# V3.net
KiCad netlist of a schematic drawn in EAGLE
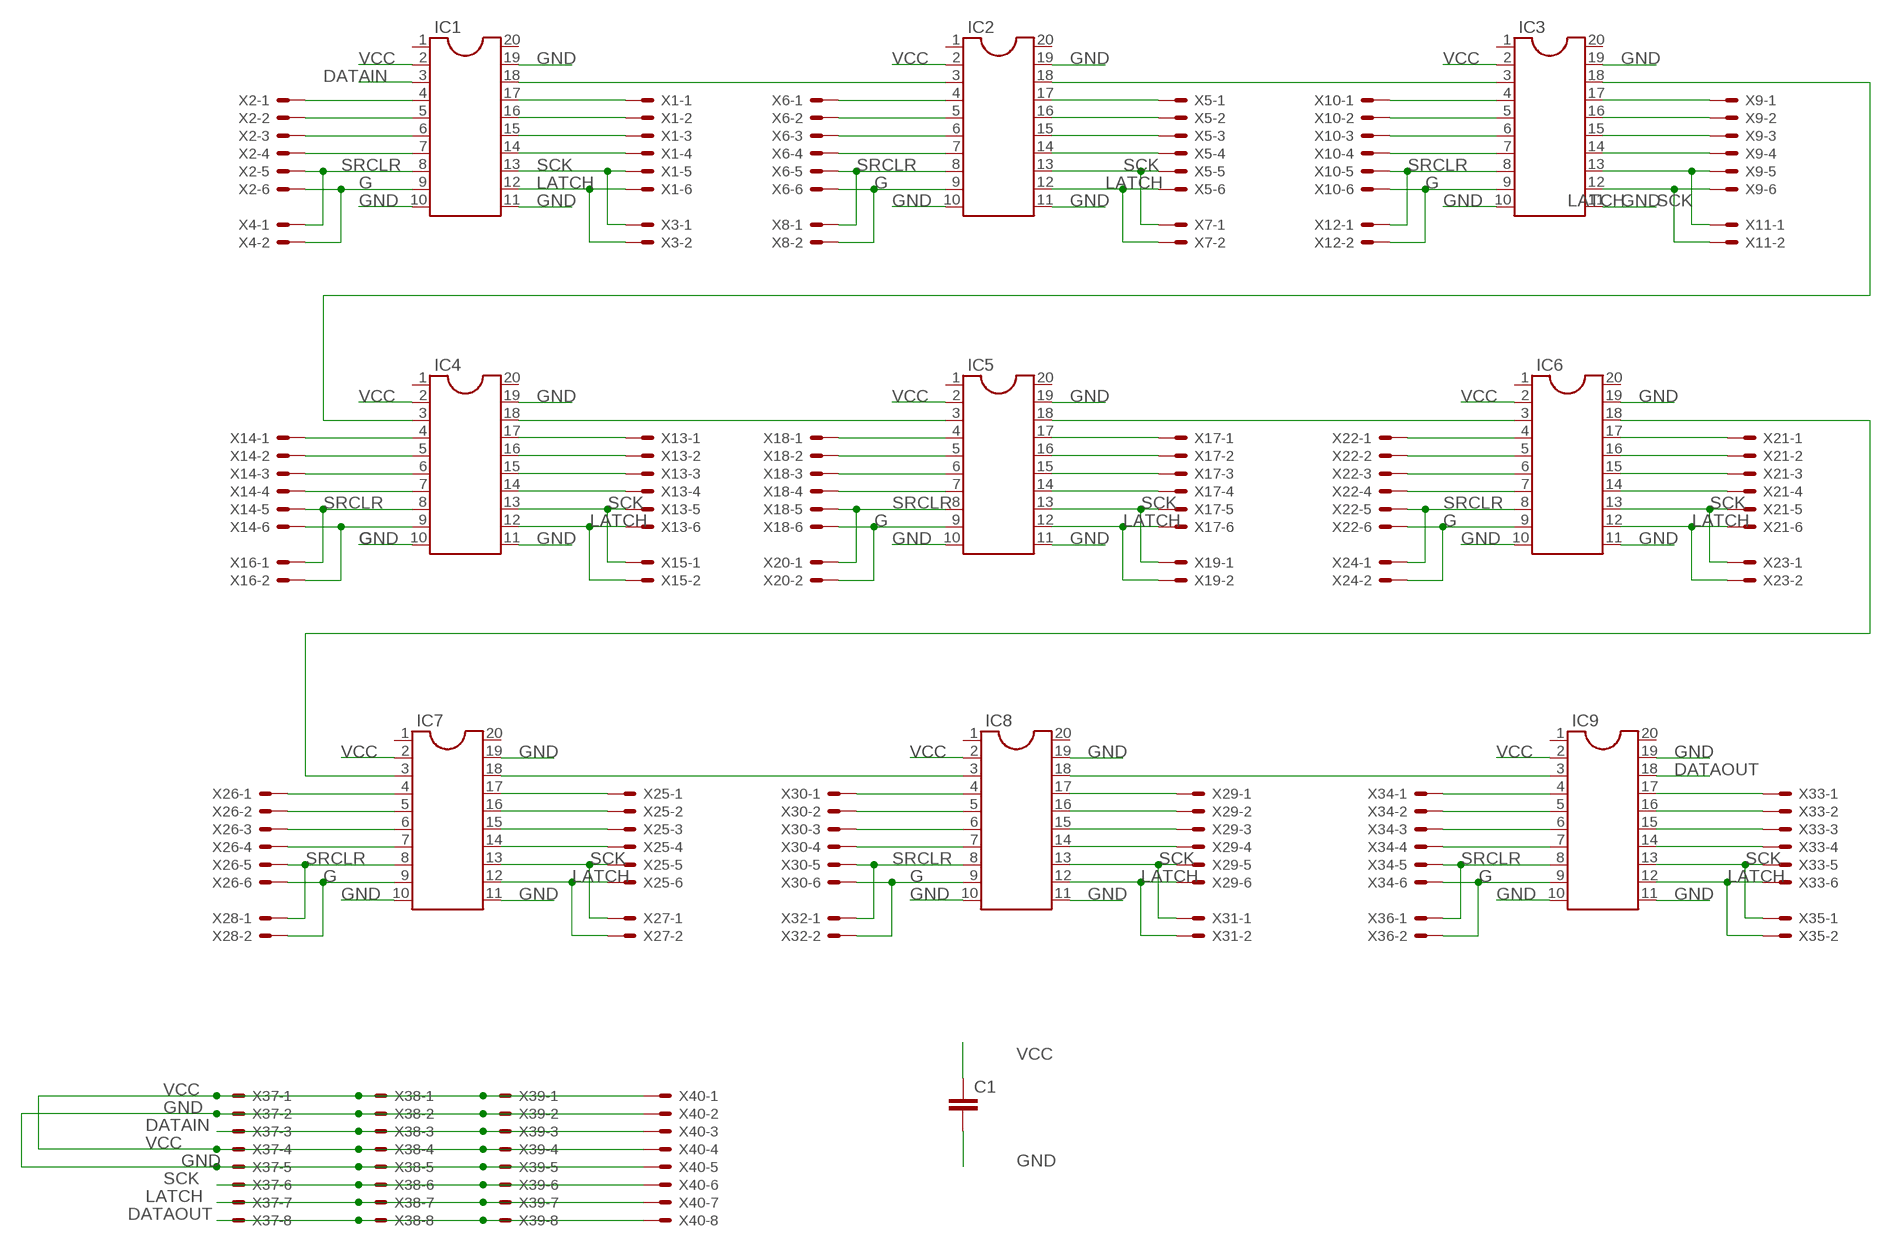
[diagram p0: schematic, sheet 1]

(export (version "E")
  (design (tool "Eeschema 10.0.6"))
  (components
    (comp (ref "C1")
      (value "C2.5/2")
      (footprint "eagle-import:C2.5-2")
      (libsource (lib "eagle-import") (part "C2.5/2"))
    )
    (comp (ref "IC1")
      (value "DIL20")
      (footprint "eagle-import:DIL20")
      (libsource (lib "eagle-import") (part "DIL20"))
    )
    (comp (ref "IC2")
      (value "DIL20")
      (footprint "eagle-import:DIL20")
      (libsource (lib "eagle-import") (part "DIL20"))
    )
    (comp (ref "IC3")
      (value "DIL20")
      (footprint "eagle-import:DIL20")
      (libsource (lib "eagle-import") (part "DIL20"))
    )
    (comp (ref "IC4")
      (value "DIL20")
      (footprint "eagle-import:DIL20")
      (libsource (lib "eagle-import") (part "DIL20"))
    )
    (comp (ref "IC5")
      (value "DIL20")
      (footprint "eagle-import:DIL20")
      (libsource (lib "eagle-import") (part "DIL20"))
    )
    (comp (ref "IC6")
      (value "DIL20")
      (footprint "eagle-import:DIL20")
      (libsource (lib "eagle-import") (part "DIL20"))
    )
    (comp (ref "IC7")
      (value "DIL20")
      (footprint "eagle-import:DIL20")
      (libsource (lib "eagle-import") (part "DIL20"))
    )
    (comp (ref "IC8")
      (value "DIL20")
      (footprint "eagle-import:DIL20")
      (libsource (lib "eagle-import") (part "DIL20"))
    )
    (comp (ref "IC9")
      (value "DIL20")
      (footprint "eagle-import:DIL20")
      (libsource (lib "eagle-import") (part "DIL20"))
    )
    (comp (ref "X1")
      (value "22-23-2061")
      (footprint "eagle-import:22-23-2061")
      (fields (field (name "MF") "MOLEX"))
      (libsource (lib "eagle-import") (part "22-23-2061"))
    )
    (comp (ref "X2")
      (value "22-23-2061")
      (footprint "eagle-import:22-23-2061")
      (fields (field (name "MF") "MOLEX"))
      (libsource (lib "eagle-import") (part "22-23-2061"))
    )
    (comp (ref "X3")
      (value "22-23-2021")
      (footprint "eagle-import:22-23-2021")
      (fields (field (name "MF") "MOLEX"))
      (libsource (lib "eagle-import") (part "22-23-2021"))
    )
    (comp (ref "X4")
      (value "22-23-2021")
      (footprint "eagle-import:22-23-2021")
      (fields (field (name "MF") "MOLEX"))
      (libsource (lib "eagle-import") (part "22-23-2021"))
    )
    (comp (ref "X5")
      (value "22-23-2061")
      (footprint "eagle-import:22-23-2061")
      (fields (field (name "MF") "MOLEX"))
      (libsource (lib "eagle-import") (part "22-23-2061"))
    )
    (comp (ref "X6")
      (value "22-23-2061")
      (footprint "eagle-import:22-23-2061")
      (fields (field (name "MF") "MOLEX"))
      (libsource (lib "eagle-import") (part "22-23-2061"))
    )
    (comp (ref "X7")
      (value "22-23-2021")
      (footprint "eagle-import:22-23-2021")
      (fields (field (name "MF") "MOLEX"))
      (libsource (lib "eagle-import") (part "22-23-2021"))
    )
    (comp (ref "X8")
      (value "22-23-2021")
      (footprint "eagle-import:22-23-2021")
      (fields (field (name "MF") "MOLEX"))
      (libsource (lib "eagle-import") (part "22-23-2021"))
    )
    (comp (ref "X9")
      (value "22-23-2061")
      (footprint "eagle-import:22-23-2061")
      (fields (field (name "MF") "MOLEX"))
      (libsource (lib "eagle-import") (part "22-23-2061"))
    )
    (comp (ref "X10")
      (value "22-23-2061")
      (footprint "eagle-import:22-23-2061")
      (fields (field (name "MF") "MOLEX"))
      (libsource (lib "eagle-import") (part "22-23-2061"))
    )
    (comp (ref "X11")
      (value "22-23-2021")
      (footprint "eagle-import:22-23-2021")
      (fields (field (name "MF") "MOLEX"))
      (libsource (lib "eagle-import") (part "22-23-2021"))
    )
    (comp (ref "X12")
      (value "22-23-2021")
      (footprint "eagle-import:22-23-2021")
      (fields (field (name "MF") "MOLEX"))
      (libsource (lib "eagle-import") (part "22-23-2021"))
    )
    (comp (ref "X13")
      (value "22-23-2061")
      (footprint "eagle-import:22-23-2061")
      (fields (field (name "MF") "MOLEX"))
      (libsource (lib "eagle-import") (part "22-23-2061"))
    )
    (comp (ref "X14")
      (value "22-23-2061")
      (footprint "eagle-import:22-23-2061")
      (fields (field (name "MF") "MOLEX"))
      (libsource (lib "eagle-import") (part "22-23-2061"))
    )
    (comp (ref "X15")
      (value "22-23-2021")
      (footprint "eagle-import:22-23-2021")
      (fields (field (name "MF") "MOLEX"))
      (libsource (lib "eagle-import") (part "22-23-2021"))
    )
    (comp (ref "X16")
      (value "22-23-2021")
      (footprint "eagle-import:22-23-2021")
      (fields (field (name "MF") "MOLEX"))
      (libsource (lib "eagle-import") (part "22-23-2021"))
    )
    (comp (ref "X17")
      (value "22-23-2061")
      (footprint "eagle-import:22-23-2061")
      (fields (field (name "MF") "MOLEX"))
      (libsource (lib "eagle-import") (part "22-23-2061"))
    )
    (comp (ref "X18")
      (value "22-23-2061")
      (footprint "eagle-import:22-23-2061")
      (fields (field (name "MF") "MOLEX"))
      (libsource (lib "eagle-import") (part "22-23-2061"))
    )
    (comp (ref "X19")
      (value "22-23-2021")
      (footprint "eagle-import:22-23-2021")
      (fields (field (name "MF") "MOLEX"))
      (libsource (lib "eagle-import") (part "22-23-2021"))
    )
    (comp (ref "X20")
      (value "22-23-2021")
      (footprint "eagle-import:22-23-2021")
      (fields (field (name "MF") "MOLEX"))
      (libsource (lib "eagle-import") (part "22-23-2021"))
    )
    (comp (ref "X21")
      (value "22-23-2061")
      (footprint "eagle-import:22-23-2061")
      (fields (field (name "MF") "MOLEX"))
      (libsource (lib "eagle-import") (part "22-23-2061"))
    )
    (comp (ref "X22")
      (value "22-23-2061")
      (footprint "eagle-import:22-23-2061")
      (fields (field (name "MF") "MOLEX"))
      (libsource (lib "eagle-import") (part "22-23-2061"))
    )
    (comp (ref "X23")
      (value "22-23-2021")
      (footprint "eagle-import:22-23-2021")
      (fields (field (name "MF") "MOLEX"))
      (libsource (lib "eagle-import") (part "22-23-2021"))
    )
    (comp (ref "X24")
      (value "22-23-2021")
      (footprint "eagle-import:22-23-2021")
      (fields (field (name "MF") "MOLEX"))
      (libsource (lib "eagle-import") (part "22-23-2021"))
    )
    (comp (ref "X25")
      (value "22-23-2061")
      (footprint "eagle-import:22-23-2061")
      (fields (field (name "MF") "MOLEX"))
      (libsource (lib "eagle-import") (part "22-23-2061"))
    )
    (comp (ref "X26")
      (value "22-23-2061")
      (footprint "eagle-import:22-23-2061")
      (fields (field (name "MF") "MOLEX"))
      (libsource (lib "eagle-import") (part "22-23-2061"))
    )
    (comp (ref "X27")
      (value "22-23-2021")
      (footprint "eagle-import:22-23-2021")
      (fields (field (name "MF") "MOLEX"))
      (libsource (lib "eagle-import") (part "22-23-2021"))
    )
    (comp (ref "X28")
      (value "22-23-2021")
      (footprint "eagle-import:22-23-2021")
      (fields (field (name "MF") "MOLEX"))
      (libsource (lib "eagle-import") (part "22-23-2021"))
    )
    (comp (ref "X29")
      (value "22-23-2061")
      (footprint "eagle-import:22-23-2061")
      (fields (field (name "MF") "MOLEX"))
      (libsource (lib "eagle-import") (part "22-23-2061"))
    )
    (comp (ref "X30")
      (value "22-23-2061")
      (footprint "eagle-import:22-23-2061")
      (fields (field (name "MF") "MOLEX"))
      (libsource (lib "eagle-import") (part "22-23-2061"))
    )
    (comp (ref "X31")
      (value "22-23-2021")
      (footprint "eagle-import:22-23-2021")
      (fields (field (name "MF") "MOLEX"))
      (libsource (lib "eagle-import") (part "22-23-2021"))
    )
    (comp (ref "X32")
      (value "22-23-2021")
      (footprint "eagle-import:22-23-2021")
      (fields (field (name "MF") "MOLEX"))
      (libsource (lib "eagle-import") (part "22-23-2021"))
    )
    (comp (ref "X33")
      (value "22-23-2061")
      (footprint "eagle-import:22-23-2061")
      (fields (field (name "MF") "MOLEX"))
      (libsource (lib "eagle-import") (part "22-23-2061"))
    )
    (comp (ref "X34")
      (value "22-23-2061")
      (footprint "eagle-import:22-23-2061")
      (fields (field (name "MF") "MOLEX"))
      (libsource (lib "eagle-import") (part "22-23-2061"))
    )
    (comp (ref "X35")
      (value "22-23-2021")
      (footprint "eagle-import:22-23-2021")
      (fields (field (name "MF") "MOLEX"))
      (libsource (lib "eagle-import") (part "22-23-2021"))
    )
    (comp (ref "X36")
      (value "22-23-2021")
      (footprint "eagle-import:22-23-2021")
      (fields (field (name "MF") "MOLEX"))
      (libsource (lib "eagle-import") (part "22-23-2021"))
    )
    (comp (ref "X37")
      (value "22-23-2081")
      (footprint "eagle-import:22-23-2081")
      (fields (field (name "MF") "MOLEX"))
      (libsource (lib "eagle-import") (part "22-23-2081"))
    )
    (comp (ref "X38")
      (value "22-23-2081")
      (footprint "eagle-import:22-23-2081")
      (fields (field (name "MF") "MOLEX"))
      (libsource (lib "eagle-import") (part "22-23-2081"))
    )
    (comp (ref "X39")
      (value "22-23-2081")
      (footprint "eagle-import:22-23-2081")
      (fields (field (name "MF") "MOLEX"))
      (libsource (lib "eagle-import") (part "22-23-2081"))
    )
    (comp (ref "X40")
      (value "22-23-2081")
      (footprint "eagle-import:22-23-2081")
      (fields (field (name "MF") "MOLEX"))
      (libsource (lib "eagle-import") (part "22-23-2081"))
    )
  )
  (nets
    (net (code "1") (name "/DATAIN") (class "Default")
      (node (ref "IC1") (pin "3") (pinfunction "3_3") (pintype "passive"))
      (node (ref "X37") (pin "3") (pinfunction "S_3") (pintype "passive"))
      (node (ref "X38") (pin "3") (pinfunction "S_3") (pintype "passive"))
      (node (ref "X39") (pin "3") (pinfunction "S_3") (pintype "passive"))
      (node (ref "X40") (pin "3") (pinfunction "S_3") (pintype "passive"))
    )
    (net (code "2") (name "/DATAOUT") (class "Default")
      (node (ref "IC9") (pin "18") (pinfunction "18_18") (pintype "passive"))
      (node (ref "X37") (pin "8") (pinfunction "S_8") (pintype "passive"))
      (node (ref "X38") (pin "8") (pinfunction "S_8") (pintype "passive"))
      (node (ref "X39") (pin "8") (pinfunction "S_8") (pintype "passive"))
      (node (ref "X40") (pin "8") (pinfunction "S_8") (pintype "passive"))
    )
    (net (code "3") (name "/G") (class "Default")
      (node (ref "IC1") (pin "9") (pinfunction "9_9") (pintype "passive"))
      (node (ref "IC2") (pin "9") (pinfunction "9_9") (pintype "passive"))
      (node (ref "IC3") (pin "9") (pinfunction "9_9") (pintype "passive"))
      (node (ref "IC4") (pin "9") (pinfunction "9_9") (pintype "passive"))
      (node (ref "IC5") (pin "9") (pinfunction "9_9") (pintype "passive"))
      (node (ref "IC6") (pin "9") (pinfunction "9_9") (pintype "passive"))
      (node (ref "IC7") (pin "9") (pinfunction "9_9") (pintype "passive"))
      (node (ref "IC8") (pin "9") (pinfunction "9_9") (pintype "passive"))
      (node (ref "IC9") (pin "9") (pinfunction "9_9") (pintype "passive"))
      (node (ref "X10") (pin "6") (pinfunction "S_6") (pintype "passive"))
      (node (ref "X12") (pin "2") (pinfunction "S_2") (pintype "passive"))
      (node (ref "X14") (pin "6") (pinfunction "S_6") (pintype "passive"))
      (node (ref "X16") (pin "2") (pinfunction "S_2") (pintype "passive"))
      (node (ref "X18") (pin "6") (pinfunction "S_6") (pintype "passive"))
      (node (ref "X2") (pin "6") (pinfunction "S_6") (pintype "passive"))
      (node (ref "X20") (pin "2") (pinfunction "S_2") (pintype "passive"))
      (node (ref "X22") (pin "6") (pinfunction "S_6") (pintype "passive"))
      (node (ref "X24") (pin "2") (pinfunction "S_2") (pintype "passive"))
      (node (ref "X26") (pin "6") (pinfunction "S_6") (pintype "passive"))
      (node (ref "X28") (pin "2") (pinfunction "S_2") (pintype "passive"))
      (node (ref "X30") (pin "6") (pinfunction "S_6") (pintype "passive"))
      (node (ref "X32") (pin "2") (pinfunction "S_2") (pintype "passive"))
      (node (ref "X34") (pin "6") (pinfunction "S_6") (pintype "passive"))
      (node (ref "X36") (pin "2") (pinfunction "S_2") (pintype "passive"))
      (node (ref "X4") (pin "2") (pinfunction "S_2") (pintype "passive"))
      (node (ref "X6") (pin "6") (pinfunction "S_6") (pintype "passive"))
      (node (ref "X8") (pin "2") (pinfunction "S_2") (pintype "passive"))
    )
    (net (code "4") (name "/GND") (class "Default")
      (node (ref "C1") (pin "2") (pinfunction "2_2") (pintype "passive"))
      (node (ref "IC1") (pin "10") (pinfunction "10_10") (pintype "passive"))
      (node (ref "IC1") (pin "11") (pinfunction "11_11") (pintype "passive"))
      (node (ref "IC1") (pin "19") (pinfunction "19_19") (pintype "passive"))
      (node (ref "IC2") (pin "10") (pinfunction "10_10") (pintype "passive"))
      (node (ref "IC2") (pin "11") (pinfunction "11_11") (pintype "passive"))
      (node (ref "IC2") (pin "19") (pinfunction "19_19") (pintype "passive"))
      (node (ref "IC3") (pin "10") (pinfunction "10_10") (pintype "passive"))
      (node (ref "IC3") (pin "11") (pinfunction "11_11") (pintype "passive"))
      (node (ref "IC3") (pin "19") (pinfunction "19_19") (pintype "passive"))
      (node (ref "IC4") (pin "10") (pinfunction "10_10") (pintype "passive"))
      (node (ref "IC4") (pin "11") (pinfunction "11_11") (pintype "passive"))
      (node (ref "IC4") (pin "19") (pinfunction "19_19") (pintype "passive"))
      (node (ref "IC5") (pin "10") (pinfunction "10_10") (pintype "passive"))
      (node (ref "IC5") (pin "11") (pinfunction "11_11") (pintype "passive"))
      (node (ref "IC5") (pin "19") (pinfunction "19_19") (pintype "passive"))
      (node (ref "IC6") (pin "10") (pinfunction "10_10") (pintype "passive"))
      (node (ref "IC6") (pin "11") (pinfunction "11_11") (pintype "passive"))
      (node (ref "IC6") (pin "19") (pinfunction "19_19") (pintype "passive"))
      (node (ref "IC7") (pin "10") (pinfunction "10_10") (pintype "passive"))
      (node (ref "IC7") (pin "11") (pinfunction "11_11") (pintype "passive"))
      (node (ref "IC7") (pin "19") (pinfunction "19_19") (pintype "passive"))
      (node (ref "IC8") (pin "10") (pinfunction "10_10") (pintype "passive"))
      (node (ref "IC8") (pin "11") (pinfunction "11_11") (pintype "passive"))
      (node (ref "IC8") (pin "19") (pinfunction "19_19") (pintype "passive"))
      (node (ref "IC9") (pin "10") (pinfunction "10_10") (pintype "passive"))
      (node (ref "IC9") (pin "11") (pinfunction "11_11") (pintype "passive"))
      (node (ref "IC9") (pin "19") (pinfunction "19_19") (pintype "passive"))
      (node (ref "X37") (pin "2") (pinfunction "S_2") (pintype "passive"))
      (node (ref "X37") (pin "5") (pinfunction "S_5") (pintype "passive"))
      (node (ref "X38") (pin "2") (pinfunction "S_2") (pintype "passive"))
      (node (ref "X38") (pin "5") (pinfunction "S_5") (pintype "passive"))
      (node (ref "X39") (pin "2") (pinfunction "S_2") (pintype "passive"))
      (node (ref "X39") (pin "5") (pinfunction "S_5") (pintype "passive"))
      (node (ref "X40") (pin "2") (pinfunction "S_2") (pintype "passive"))
      (node (ref "X40") (pin "5") (pinfunction "S_5") (pintype "passive"))
    )
    (net (code "5") (name "/LATCH") (class "Default")
      (node (ref "IC1") (pin "12") (pinfunction "12_12") (pintype "passive"))
      (node (ref "IC2") (pin "12") (pinfunction "12_12") (pintype "passive"))
      (node (ref "IC3") (pin "12") (pinfunction "12_12") (pintype "passive"))
      (node (ref "IC4") (pin "12") (pinfunction "12_12") (pintype "passive"))
      (node (ref "IC5") (pin "12") (pinfunction "12_12") (pintype "passive"))
      (node (ref "IC6") (pin "12") (pinfunction "12_12") (pintype "passive"))
      (node (ref "IC7") (pin "12") (pinfunction "12_12") (pintype "passive"))
      (node (ref "IC8") (pin "12") (pinfunction "12_12") (pintype "passive"))
      (node (ref "IC9") (pin "12") (pinfunction "12_12") (pintype "passive"))
      (node (ref "X1") (pin "6") (pinfunction "S_6") (pintype "passive"))
      (node (ref "X11") (pin "2") (pinfunction "S_2") (pintype "passive"))
      (node (ref "X13") (pin "6") (pinfunction "S_6") (pintype "passive"))
      (node (ref "X15") (pin "2") (pinfunction "S_2") (pintype "passive"))
      (node (ref "X17") (pin "6") (pinfunction "S_6") (pintype "passive"))
      (node (ref "X19") (pin "2") (pinfunction "S_2") (pintype "passive"))
      (node (ref "X21") (pin "6") (pinfunction "S_6") (pintype "passive"))
      (node (ref "X23") (pin "2") (pinfunction "S_2") (pintype "passive"))
      (node (ref "X25") (pin "6") (pinfunction "S_6") (pintype "passive"))
      (node (ref "X27") (pin "2") (pinfunction "S_2") (pintype "passive"))
      (node (ref "X29") (pin "6") (pinfunction "S_6") (pintype "passive"))
      (node (ref "X3") (pin "2") (pinfunction "S_2") (pintype "passive"))
      (node (ref "X31") (pin "2") (pinfunction "S_2") (pintype "passive"))
      (node (ref "X33") (pin "6") (pinfunction "S_6") (pintype "passive"))
      (node (ref "X35") (pin "2") (pinfunction "S_2") (pintype "passive"))
      (node (ref "X37") (pin "7") (pinfunction "S_7") (pintype "passive"))
      (node (ref "X38") (pin "7") (pinfunction "S_7") (pintype "passive"))
      (node (ref "X39") (pin "7") (pinfunction "S_7") (pintype "passive"))
      (node (ref "X40") (pin "7") (pinfunction "S_7") (pintype "passive"))
      (node (ref "X5") (pin "6") (pinfunction "S_6") (pintype "passive"))
      (node (ref "X7") (pin "2") (pinfunction "S_2") (pintype "passive"))
      (node (ref "X9") (pin "6") (pinfunction "S_6") (pintype "passive"))
    )
    (net (code "6") (name "/SCK") (class "Default")
      (node (ref "IC1") (pin "13") (pinfunction "13_13") (pintype "passive"))
      (node (ref "IC2") (pin "13") (pinfunction "13_13") (pintype "passive"))
      (node (ref "IC3") (pin "13") (pinfunction "13_13") (pintype "passive"))
      (node (ref "IC4") (pin "13") (pinfunction "13_13") (pintype "passive"))
      (node (ref "IC5") (pin "13") (pinfunction "13_13") (pintype "passive"))
      (node (ref "IC6") (pin "13") (pinfunction "13_13") (pintype "passive"))
      (node (ref "IC7") (pin "13") (pinfunction "13_13") (pintype "passive"))
      (node (ref "IC8") (pin "13") (pinfunction "13_13") (pintype "passive"))
      (node (ref "IC9") (pin "13") (pinfunction "13_13") (pintype "passive"))
      (node (ref "X1") (pin "5") (pinfunction "S_5") (pintype "passive"))
      (node (ref "X11") (pin "1") (pinfunction "S_1") (pintype "passive"))
      (node (ref "X13") (pin "5") (pinfunction "S_5") (pintype "passive"))
      (node (ref "X15") (pin "1") (pinfunction "S_1") (pintype "passive"))
      (node (ref "X17") (pin "5") (pinfunction "S_5") (pintype "passive"))
      (node (ref "X19") (pin "1") (pinfunction "S_1") (pintype "passive"))
      (node (ref "X21") (pin "5") (pinfunction "S_5") (pintype "passive"))
      (node (ref "X23") (pin "1") (pinfunction "S_1") (pintype "passive"))
      (node (ref "X25") (pin "5") (pinfunction "S_5") (pintype "passive"))
      (node (ref "X27") (pin "1") (pinfunction "S_1") (pintype "passive"))
      (node (ref "X29") (pin "5") (pinfunction "S_5") (pintype "passive"))
      (node (ref "X3") (pin "1") (pinfunction "S_1") (pintype "passive"))
      (node (ref "X31") (pin "1") (pinfunction "S_1") (pintype "passive"))
      (node (ref "X33") (pin "5") (pinfunction "S_5") (pintype "passive"))
      (node (ref "X35") (pin "1") (pinfunction "S_1") (pintype "passive"))
      (node (ref "X37") (pin "6") (pinfunction "S_6") (pintype "passive"))
      (node (ref "X38") (pin "6") (pinfunction "S_6") (pintype "passive"))
      (node (ref "X39") (pin "6") (pinfunction "S_6") (pintype "passive"))
      (node (ref "X40") (pin "6") (pinfunction "S_6") (pintype "passive"))
      (node (ref "X5") (pin "5") (pinfunction "S_5") (pintype "passive"))
      (node (ref "X7") (pin "1") (pinfunction "S_1") (pintype "passive"))
      (node (ref "X9") (pin "5") (pinfunction "S_5") (pintype "passive"))
    )
    (net (code "7") (name "/SRCLR") (class "Default")
      (node (ref "IC1") (pin "8") (pinfunction "8_8") (pintype "passive"))
      (node (ref "IC2") (pin "8") (pinfunction "8_8") (pintype "passive"))
      (node (ref "IC3") (pin "8") (pinfunction "8_8") (pintype "passive"))
      (node (ref "IC4") (pin "8") (pinfunction "8_8") (pintype "passive"))
      (node (ref "IC5") (pin "8") (pinfunction "8_8") (pintype "passive"))
      (node (ref "IC6") (pin "8") (pinfunction "8_8") (pintype "passive"))
      (node (ref "IC7") (pin "8") (pinfunction "8_8") (pintype "passive"))
      (node (ref "IC8") (pin "8") (pinfunction "8_8") (pintype "passive"))
      (node (ref "IC9") (pin "8") (pinfunction "8_8") (pintype "passive"))
      (node (ref "X10") (pin "5") (pinfunction "S_5") (pintype "passive"))
      (node (ref "X12") (pin "1") (pinfunction "S_1") (pintype "passive"))
      (node (ref "X14") (pin "5") (pinfunction "S_5") (pintype "passive"))
      (node (ref "X16") (pin "1") (pinfunction "S_1") (pintype "passive"))
      (node (ref "X18") (pin "5") (pinfunction "S_5") (pintype "passive"))
      (node (ref "X2") (pin "5") (pinfunction "S_5") (pintype "passive"))
      (node (ref "X20") (pin "1") (pinfunction "S_1") (pintype "passive"))
      (node (ref "X22") (pin "5") (pinfunction "S_5") (pintype "passive"))
      (node (ref "X24") (pin "1") (pinfunction "S_1") (pintype "passive"))
      (node (ref "X26") (pin "5") (pinfunction "S_5") (pintype "passive"))
      (node (ref "X28") (pin "1") (pinfunction "S_1") (pintype "passive"))
      (node (ref "X30") (pin "5") (pinfunction "S_5") (pintype "passive"))
      (node (ref "X32") (pin "1") (pinfunction "S_1") (pintype "passive"))
      (node (ref "X34") (pin "5") (pinfunction "S_5") (pintype "passive"))
      (node (ref "X36") (pin "1") (pinfunction "S_1") (pintype "passive"))
      (node (ref "X4") (pin "1") (pinfunction "S_1") (pintype "passive"))
      (node (ref "X6") (pin "5") (pinfunction "S_5") (pintype "passive"))
      (node (ref "X8") (pin "1") (pinfunction "S_1") (pintype "passive"))
    )
    (net (code "8") (name "/VCC") (class "Default")
      (node (ref "C1") (pin "1") (pinfunction "1_1") (pintype "passive"))
      (node (ref "IC1") (pin "2") (pinfunction "2_2") (pintype "passive"))
      (node (ref "IC2") (pin "2") (pinfunction "2_2") (pintype "passive"))
      (node (ref "IC3") (pin "2") (pinfunction "2_2") (pintype "passive"))
      (node (ref "IC4") (pin "2") (pinfunction "2_2") (pintype "passive"))
      (node (ref "IC5") (pin "2") (pinfunction "2_2") (pintype "passive"))
      (node (ref "IC6") (pin "2") (pinfunction "2_2") (pintype "passive"))
      (node (ref "IC7") (pin "2") (pinfunction "2_2") (pintype "passive"))
      (node (ref "IC8") (pin "2") (pinfunction "2_2") (pintype "passive"))
      (node (ref "IC9") (pin "2") (pinfunction "2_2") (pintype "passive"))
      (node (ref "X37") (pin "1") (pinfunction "S_1") (pintype "passive"))
      (node (ref "X37") (pin "4") (pinfunction "S_4") (pintype "passive"))
      (node (ref "X38") (pin "1") (pinfunction "S_1") (pintype "passive"))
      (node (ref "X38") (pin "4") (pinfunction "S_4") (pintype "passive"))
      (node (ref "X39") (pin "1") (pinfunction "S_1") (pintype "passive"))
      (node (ref "X39") (pin "4") (pinfunction "S_4") (pintype "passive"))
      (node (ref "X40") (pin "1") (pinfunction "S_1") (pintype "passive"))
      (node (ref "X40") (pin "4") (pinfunction "S_4") (pintype "passive"))
    )
    (net (code "9") (name "Net-(IC1-Pad18)") (class "Default")
      (node (ref "IC1") (pin "18") (pinfunction "18_18") (pintype "passive"))
      (node (ref "IC2") (pin "3") (pinfunction "3_3") (pintype "passive"))
    )
    (net (code "10") (name "Net-(IC2-Pad18)") (class "Default")
      (node (ref "IC2") (pin "18") (pinfunction "18_18") (pintype "passive"))
      (node (ref "IC3") (pin "3") (pinfunction "3_3") (pintype "passive"))
    )
    (net (code "11") (name "Net-(IC3-Pad18)") (class "Default")
      (node (ref "IC3") (pin "18") (pinfunction "18_18") (pintype "passive"))
      (node (ref "IC4") (pin "3") (pinfunction "3_3") (pintype "passive"))
    )
    (net (code "12") (name "Net-(IC4-Pad18)") (class "Default")
      (node (ref "IC4") (pin "18") (pinfunction "18_18") (pintype "passive"))
      (node (ref "IC5") (pin "3") (pinfunction "3_3") (pintype "passive"))
    )
    (net (code "13") (name "Net-(IC5-Pad18)") (class "Default")
      (node (ref "IC5") (pin "18") (pinfunction "18_18") (pintype "passive"))
      (node (ref "IC6") (pin "3") (pinfunction "3_3") (pintype "passive"))
    )
    (net (code "14") (name "Net-(IC6-Pad18)") (class "Default")
      (node (ref "IC6") (pin "18") (pinfunction "18_18") (pintype "passive"))
      (node (ref "IC7") (pin "3") (pinfunction "3_3") (pintype "passive"))
    )
    (net (code "15") (name "Net-(IC7-Pad18)") (class "Default")
      (node (ref "IC7") (pin "18") (pinfunction "18_18") (pintype "passive"))
      (node (ref "IC8") (pin "3") (pinfunction "3_3") (pintype "passive"))
    )
    (net (code "16") (name "Net-(IC8-Pad18)") (class "Default")
      (node (ref "IC8") (pin "18") (pinfunction "18_18") (pintype "passive"))
      (node (ref "IC9") (pin "3") (pinfunction "3_3") (pintype "passive"))
    )
    (net (code "17") (name "Net-(X1A-S)") (class "Default")
      (node (ref "IC1") (pin "17") (pinfunction "17_17") (pintype "passive"))
      (node (ref "X1") (pin "1") (pinfunction "S_1") (pintype "passive"))
    )
    (net (code "18") (name "Net-(X1B-S)") (class "Default")
      (node (ref "IC1") (pin "16") (pinfunction "16_16") (pintype "passive"))
      (node (ref "X1") (pin "2") (pinfunction "S_2") (pintype "passive"))
    )
    (net (code "19") (name "Net-(X1C-S)") (class "Default")
      (node (ref "IC1") (pin "15") (pinfunction "15_15") (pintype "passive"))
      (node (ref "X1") (pin "3") (pinfunction "S_3") (pintype "passive"))
    )
    (net (code "20") (name "Net-(X1D-S)") (class "Default")
      (node (ref "IC1") (pin "14") (pinfunction "14_14") (pintype "passive"))
      (node (ref "X1") (pin "4") (pinfunction "S_4") (pintype "passive"))
    )
    (net (code "21") (name "Net-(X2A-S)") (class "Default")
      (node (ref "IC1") (pin "4") (pinfunction "4_4") (pintype "passive"))
      (node (ref "X2") (pin "1") (pinfunction "S_1") (pintype "passive"))
    )
    (net (code "22") (name "Net-(X2B-S)") (class "Default")
      (node (ref "IC1") (pin "5") (pinfunction "5_5") (pintype "passive"))
      (node (ref "X2") (pin "2") (pinfunction "S_2") (pintype "passive"))
    )
    (net (code "23") (name "Net-(X2C-S)") (class "Default")
      (node (ref "IC1") (pin "6") (pinfunction "6_6") (pintype "passive"))
      (node (ref "X2") (pin "3") (pinfunction "S_3") (pintype "passive"))
    )
    (net (code "24") (name "Net-(X2D-S)") (class "Default")
      (node (ref "IC1") (pin "7") (pinfunction "7_7") (pintype "passive"))
      (node (ref "X2") (pin "4") (pinfunction "S_4") (pintype "passive"))
    )
    (net (code "25") (name "Net-(X5A-S)") (class "Default")
      (node (ref "IC2") (pin "17") (pinfunction "17_17") (pintype "passive"))
      (node (ref "X5") (pin "1") (pinfunction "S_1") (pintype "passive"))
    )
    (net (code "26") (name "Net-(X5B-S)") (class "Default")
      (node (ref "IC2") (pin "16") (pinfunction "16_16") (pintype "passive"))
      (node (ref "X5") (pin "2") (pinfunction "S_2") (pintype "passive"))
    )
    (net (code "27") (name "Net-(X5C-S)") (class "Default")
      (node (ref "IC2") (pin "15") (pinfunction "15_15") (pintype "passive"))
      (node (ref "X5") (pin "3") (pinfunction "S_3") (pintype "passive"))
    )
    (net (code "28") (name "Net-(X5D-S)") (class "Default")
      (node (ref "IC2") (pin "14") (pinfunction "14_14") (pintype "passive"))
      (node (ref "X5") (pin "4") (pinfunction "S_4") (pintype "passive"))
    )
    (net (code "29") (name "Net-(X6A-S)") (class "Default")
      (node (ref "IC2") (pin "4") (pinfunction "4_4") (pintype "passive"))
      (node (ref "X6") (pin "1") (pinfunction "S_1") (pintype "passive"))
    )
    (net (code "30") (name "Net-(X6B-S)") (class "Default")
      (node (ref "IC2") (pin "5") (pinfunction "5_5") (pintype "passive"))
      (node (ref "X6") (pin "2") (pinfunction "S_2") (pintype "passive"))
    )
    (net (code "31") (name "Net-(X6C-S)") (class "Default")
      (node (ref "IC2") (pin "6") (pinfunction "6_6") (pintype "passive"))
      (node (ref "X6") (pin "3") (pinfunction "S_3") (pintype "passive"))
    )
    (net (code "32") (name "Net-(X6D-S)") (class "Default")
      (node (ref "IC2") (pin "7") (pinfunction "7_7") (pintype "passive"))
      (node (ref "X6") (pin "4") (pinfunction "S_4") (pintype "passive"))
    )
    (net (code "33") (name "Net-(X9A-S)") (class "Default")
      (node (ref "IC3") (pin "17") (pinfunction "17_17") (pintype "passive"))
      (node (ref "X9") (pin "1") (pinfunction "S_1") (pintype "passive"))
    )
    (net (code "34") (name "Net-(X9B-S)") (class "Default")
      (node (ref "IC3") (pin "16") (pinfunction "16_16") (pintype "passive"))
      (node (ref "X9") (pin "2") (pinfunction "S_2") (pintype "passive"))
    )
    (net (code "35") (name "Net-(X9C-S)") (class "Default")
      (node (ref "IC3") (pin "15") (pinfunction "15_15") (pintype "passive"))
      (node (ref "X9") (pin "3") (pinfunction "S_3") (pintype "passive"))
    )
    (net (code "36") (name "Net-(X9D-S)") (class "Default")
      (node (ref "IC3") (pin "14") (pinfunction "14_14") (pintype "passive"))
      (node (ref "X9") (pin "4") (pinfunction "S_4") (pintype "passive"))
    )
    (net (code "37") (name "Net-(X10A-S)") (class "Default")
      (node (ref "IC3") (pin "4") (pinfunction "4_4") (pintype "passive"))
      (node (ref "X10") (pin "1") (pinfunction "S_1") (pintype "passive"))
    )
    (net (code "38") (name "Net-(X10B-S)") (class "Default")
      (node (ref "IC3") (pin "5") (pinfunction "5_5") (pintype "passive"))
      (node (ref "X10") (pin "2") (pinfunction "S_2") (pintype "passive"))
    )
    (net (code "39") (name "Net-(X10C-S)") (class "Default")
      (node (ref "IC3") (pin "6") (pinfunction "6_6") (pintype "passive"))
      (node (ref "X10") (pin "3") (pinfunction "S_3") (pintype "passive"))
    )
    (net (code "40") (name "Net-(X10D-S)") (class "Default")
      (node (ref "IC3") (pin "7") (pinfunction "7_7") (pintype "passive"))
      (node (ref "X10") (pin "4") (pinfunction "S_4") (pintype "passive"))
    )
    (net (code "41") (name "Net-(X13A-S)") (class "Default")
      (node (ref "IC4") (pin "17") (pinfunction "17_17") (pintype "passive"))
      (node (ref "X13") (pin "1") (pinfunction "S_1") (pintype "passive"))
    )
    (net (code "42") (name "Net-(X13B-S)") (class "Default")
      (node (ref "IC4") (pin "16") (pinfunction "16_16") (pintype "passive"))
      (node (ref "X13") (pin "2") (pinfunction "S_2") (pintype "passive"))
    )
    (net (code "43") (name "Net-(X13C-S)") (class "Default")
      (node (ref "IC4") (pin "15") (pinfunction "15_15") (pintype "passive"))
      (node (ref "X13") (pin "3") (pinfunction "S_3") (pintype "passive"))
    )
    (net (code "44") (name "Net-(X13D-S)") (class "Default")
      (node (ref "IC4") (pin "14") (pinfunction "14_14") (pintype "passive"))
      (node (ref "X13") (pin "4") (pinfunction "S_4") (pintype "passive"))
    )
    (net (code "45") (name "Net-(X14A-S)") (class "Default")
      (node (ref "IC4") (pin "4") (pinfunction "4_4") (pintype "passive"))
      (node (ref "X14") (pin "1") (pinfunction "S_1") (pintype "passive"))
    )
    (net (code "46") (name "Net-(X14B-S)") (class "Default")
      (node (ref "IC4") (pin "5") (pinfunction "5_5") (pintype "passive"))
      (node (ref "X14") (pin "2") (pinfunction "S_2") (pintype "passive"))
    )
    (net (code "47") (name "Net-(X14C-S)") (class "Default")
      (node (ref "IC4") (pin "6") (pinfunction "6_6") (pintype "passive"))
      (node (ref "X14") (pin "3") (pinfunction "S_3") (pintype "passive"))
    )
    (net (code "48") (name "Net-(X14D-S)") (class "Default")
      (node (ref "IC4") (pin "7") (pinfunction "7_7") (pintype "passive"))
      (node (ref "X14") (pin "4") (pinfunction "S_4") (pintype "passive"))
    )
    (net (code "49") (name "Net-(X17A-S)") (class "Default")
      (node (ref "IC5") (pin "17") (pinfunction "17_17") (pintype "passive"))
      (node (ref "X17") (pin "1") (pinfunction "S_1") (pintype "passive"))
    )
    (net (code "50") (name "Net-(X17B-S)") (class "Default")
      (node (ref "IC5") (pin "16") (pinfunction "16_16") (pintype "passive"))
      (node (ref "X17") (pin "2") (pinfunction "S_2") (pintype "passive"))
    )
    (net (code "51") (name "Net-(X17C-S)") (class "Default")
      (node (ref "IC5") (pin "15") (pinfunction "15_15") (pintype "passive"))
      (node (ref "X17") (pin "3") (pinfunction "S_3") (pintype "passive"))
    )
    (net (code "52") (name "Net-(X17D-S)") (class "Default")
      (node (ref "IC5") (pin "14") (pinfunction "14_14") (pintype "passive"))
      (node (ref "X17") (pin "4") (pinfunction "S_4") (pintype "passive"))
    )
    (net (code "53") (name "Net-(X18A-S)") (class "Default")
      (node (ref "IC5") (pin "4") (pinfunction "4_4") (pintype "passive"))
      (node (ref "X18") (pin "1") (pinfunction "S_1") (pintype "passive"))
    )
    (net (code "54") (name "Net-(X18B-S)") (class "Default")
      (node (ref "IC5") (pin "5") (pinfunction "5_5") (pintype "passive"))
      (node (ref "X18") (pin "2") (pinfunction "S_2") (pintype "passive"))
    )
    (net (code "55") (name "Net-(X18C-S)") (class "Default")
      (node (ref "IC5") (pin "6") (pinfunction "6_6") (pintype "passive"))
      (node (ref "X18") (pin "3") (pinfunction "S_3") (pintype "passive"))
    )
    (net (code "56") (name "Net-(X18D-S)") (class "Default")
      (node (ref "IC5") (pin "7") (pinfunction "7_7") (pintype "passive"))
      (node (ref "X18") (pin "4") (pinfunction "S_4") (pintype "passive"))
    )
    (net (code "57") (name "Net-(X21A-S)") (class "Default")
      (node (ref "IC6") (pin "17") (pinfunction "17_17") (pintype "passive"))
      (node (ref "X21") (pin "1") (pinfunction "S_1") (pintype "passive"))
    )
    (net (code "58") (name "Net-(X21B-S)") (class "Default")
      (node (ref "IC6") (pin "16") (pinfunction "16_16") (pintype "passive"))
      (node (ref "X21") (pin "2") (pinfunction "S_2") (pintype "passive"))
    )
    (net (code "59") (name "Net-(X21C-S)") (class "Default")
      (node (ref "IC6") (pin "15") (pinfunction "15_15") (pintype "passive"))
      (node (ref "X21") (pin "3") (pinfunction "S_3") (pintype "passive"))
    )
    (net (code "60") (name "Net-(X21D-S)") (class "Default")
      (node (ref "IC6") (pin "14") (pinfunction "14_14") (pintype "passive"))
      (node (ref "X21") (pin "4") (pinfunction "S_4") (pintype "passive"))
    )
    (net (code "61") (name "Net-(X22A-S)") (class "Default")
      (node (ref "IC6") (pin "4") (pinfunction "4_4") (pintype "passive"))
      (node (ref "X22") (pin "1") (pinfunction "S_1") (pintype "passive"))
    )
    (net (code "62") (name "Net-(X22B-S)") (class "Default")
      (node (ref "IC6") (pin "5") (pinfunction "5_5") (pintype "passive"))
      (node (ref "X22") (pin "2") (pinfunction "S_2") (pintype "passive"))
    )
    (net (code "63") (name "Net-(X22C-S)") (class "Default")
      (node (ref "IC6") (pin "6") (pinfunction "6_6") (pintype "passive"))
      (node (ref "X22") (pin "3") (pinfunction "S_3") (pintype "passive"))
    )
    (net (code "64") (name "Net-(X22D-S)") (class "Default")
      (node (ref "IC6") (pin "7") (pinfunction "7_7") (pintype "passive"))
      (node (ref "X22") (pin "4") (pinfunction "S_4") (pintype "passive"))
    )
    (net (code "65") (name "Net-(X25A-S)") (class "Default")
      (node (ref "IC7") (pin "17") (pinfunction "17_17") (pintype "passive"))
      (node (ref "X25") (pin "1") (pinfunction "S_1") (pintype "passive"))
    )
    (net (code "66") (name "Net-(X25B-S)") (class "Default")
      (node (ref "IC7") (pin "16") (pinfunction "16_16") (pintype "passive"))
      (node (ref "X25") (pin "2") (pinfunction "S_2") (pintype "passive"))
    )
    (net (code "67") (name "Net-(X25C-S)") (class "Default")
      (node (ref "IC7") (pin "15") (pinfunction "15_15") (pintype "passive"))
      (node (ref "X25") (pin "3") (pinfunction "S_3") (pintype "passive"))
    )
    (net (code "68") (name "Net-(X25D-S)") (class "Default")
      (node (ref "IC7") (pin "14") (pinfunction "14_14") (pintype "passive"))
      (node (ref "X25") (pin "4") (pinfunction "S_4") (pintype "passive"))
    )
    (net (code "69") (name "Net-(X26A-S)") (class "Default")
      (node (ref "IC7") (pin "4") (pinfunction "4_4") (pintype "passive"))
      (node (ref "X26") (pin "1") (pinfunction "S_1") (pintype "passive"))
    )
    (net (code "70") (name "Net-(X26B-S)") (class "Default")
      (node (ref "IC7") (pin "5") (pinfunction "5_5") (pintype "passive"))
      (node (ref "X26") (pin "2") (pinfunction "S_2") (pintype "passive"))
    )
    (net (code "71") (name "Net-(X26C-S)") (class "Default")
      (node (ref "IC7") (pin "6") (pinfunction "6_6") (pintype "passive"))
      (node (ref "X26") (pin "3") (pinfunction "S_3") (pintype "passive"))
    )
    (net (code "72") (name "Net-(X26D-S)") (class "Default")
      (node (ref "IC7") (pin "7") (pinfunction "7_7") (pintype "passive"))
      (node (ref "X26") (pin "4") (pinfunction "S_4") (pintype "passive"))
    )
    (net (code "73") (name "Net-(X29A-S)") (class "Default")
      (node (ref "IC8") (pin "17") (pinfunction "17_17") (pintype "passive"))
      (node (ref "X29") (pin "1") (pinfunction "S_1") (pintype "passive"))
    )
    (net (code "74") (name "Net-(X29B-S)") (class "Default")
      (node (ref "IC8") (pin "16") (pinfunction "16_16") (pintype "passive"))
      (node (ref "X29") (pin "2") (pinfunction "S_2") (pintype "passive"))
    )
    (net (code "75") (name "Net-(X29C-S)") (class "Default")
      (node (ref "IC8") (pin "15") (pinfunction "15_15") (pintype "passive"))
      (node (ref "X29") (pin "3") (pinfunction "S_3") (pintype "passive"))
    )
    (net (code "76") (name "Net-(X29D-S)") (class "Default")
      (node (ref "IC8") (pin "14") (pinfunction "14_14") (pintype "passive"))
      (node (ref "X29") (pin "4") (pinfunction "S_4") (pintype "passive"))
    )
    (net (code "77") (name "Net-(X30A-S)") (class "Default")
      (node (ref "IC8") (pin "4") (pinfunction "4_4") (pintype "passive"))
      (node (ref "X30") (pin "1") (pinfunction "S_1") (pintype "passive"))
    )
    (net (code "78") (name "Net-(X30B-S)") (class "Default")
      (node (ref "IC8") (pin "5") (pinfunction "5_5") (pintype "passive"))
      (node (ref "X30") (pin "2") (pinfunction "S_2") (pintype "passive"))
    )
    (net (code "79") (name "Net-(X30C-S)") (class "Default")
      (node (ref "IC8") (pin "6") (pinfunction "6_6") (pintype "passive"))
      (node (ref "X30") (pin "3") (pinfunction "S_3") (pintype "passive"))
    )
    (net (code "80") (name "Net-(X30D-S)") (class "Default")
      (node (ref "IC8") (pin "7") (pinfunction "7_7") (pintype "passive"))
      (node (ref "X30") (pin "4") (pinfunction "S_4") (pintype "passive"))
    )
    (net (code "81") (name "Net-(X33A-S)") (class "Default")
      (node (ref "IC9") (pin "17") (pinfunction "17_17") (pintype "passive"))
      (node (ref "X33") (pin "1") (pinfunction "S_1") (pintype "passive"))
    )
    (net (code "82") (name "Net-(X33B-S)") (class "Default")
      (node (ref "IC9") (pin "16") (pinfunction "16_16") (pintype "passive"))
      (node (ref "X33") (pin "2") (pinfunction "S_2") (pintype "passive"))
    )
    (net (code "83") (name "Net-(X33C-S)") (class "Default")
      (node (ref "IC9") (pin "15") (pinfunction "15_15") (pintype "passive"))
      (node (ref "X33") (pin "3") (pinfunction "S_3") (pintype "passive"))
    )
    (net (code "84") (name "Net-(X33D-S)") (class "Default")
      (node (ref "IC9") (pin "14") (pinfunction "14_14") (pintype "passive"))
      (node (ref "X33") (pin "4") (pinfunction "S_4") (pintype "passive"))
    )
    (net (code "85") (name "Net-(X34A-S)") (class "Default")
      (node (ref "IC9") (pin "4") (pinfunction "4_4") (pintype "passive"))
      (node (ref "X34") (pin "1") (pinfunction "S_1") (pintype "passive"))
    )
    (net (code "86") (name "Net-(X34B-S)") (class "Default")
      (node (ref "IC9") (pin "5") (pinfunction "5_5") (pintype "passive"))
      (node (ref "X34") (pin "2") (pinfunction "S_2") (pintype "passive"))
    )
    (net (code "87") (name "Net-(X34C-S)") (class "Default")
      (node (ref "IC9") (pin "6") (pinfunction "6_6") (pintype "passive"))
      (node (ref "X34") (pin "3") (pinfunction "S_3") (pintype "passive"))
    )
    (net (code "88") (name "Net-(X34D-S)") (class "Default")
      (node (ref "IC9") (pin "7") (pinfunction "7_7") (pintype "passive"))
      (node (ref "X34") (pin "4") (pinfunction "S_4") (pintype "passive"))
    )
    (net (code "89") (name "unconnected-(IC1-Pad1)") (class "Default")
      (node (ref "IC1") (pin "1") (pinfunction "1_1") (pintype "passive"))
    )
    (net (code "90") (name "unconnected-(IC1-Pad20)") (class "Default")
      (node (ref "IC1") (pin "20") (pinfunction "20_20") (pintype "passive"))
    )
    (net (code "91") (name "unconnected-(IC2-Pad1)") (class "Default")
      (node (ref "IC2") (pin "1") (pinfunction "1_1") (pintype "passive"))
    )
    (net (code "92") (name "unconnected-(IC2-Pad20)") (class "Default")
      (node (ref "IC2") (pin "20") (pinfunction "20_20") (pintype "passive"))
    )
    (net (code "93") (name "unconnected-(IC3-Pad1)") (class "Default")
      (node (ref "IC3") (pin "1") (pinfunction "1_1") (pintype "passive"))
    )
    (net (code "94") (name "unconnected-(IC3-Pad20)") (class "Default")
      (node (ref "IC3") (pin "20") (pinfunction "20_20") (pintype "passive"))
    )
    (net (code "95") (name "unconnected-(IC4-Pad1)") (class "Default")
      (node (ref "IC4") (pin "1") (pinfunction "1_1") (pintype "passive"))
    )
    (net (code "96") (name "unconnected-(IC4-Pad20)") (class "Default")
      (node (ref "IC4") (pin "20") (pinfunction "20_20") (pintype "passive"))
    )
    (net (code "97") (name "unconnected-(IC5-Pad1)") (class "Default")
      (node (ref "IC5") (pin "1") (pinfunction "1_1") (pintype "passive"))
    )
    (net (code "98") (name "unconnected-(IC5-Pad20)") (class "Default")
      (node (ref "IC5") (pin "20") (pinfunction "20_20") (pintype "passive"))
    )
    (net (code "99") (name "unconnected-(IC6-Pad1)") (class "Default")
      (node (ref "IC6") (pin "1") (pinfunction "1_1") (pintype "passive"))
    )
    (net (code "100") (name "unconnected-(IC6-Pad20)") (class "Default")
      (node (ref "IC6") (pin "20") (pinfunction "20_20") (pintype "passive"))
    )
    (net (code "101") (name "unconnected-(IC7-Pad1)") (class "Default")
      (node (ref "IC7") (pin "1") (pinfunction "1_1") (pintype "passive"))
    )
    (net (code "102") (name "unconnected-(IC7-Pad20)") (class "Default")
      (node (ref "IC7") (pin "20") (pinfunction "20_20") (pintype "passive"))
    )
    (net (code "103") (name "unconnected-(IC8-Pad1)") (class "Default")
      (node (ref "IC8") (pin "1") (pinfunction "1_1") (pintype "passive"))
    )
    (net (code "104") (name "unconnected-(IC8-Pad20)") (class "Default")
      (node (ref "IC8") (pin "20") (pinfunction "20_20") (pintype "passive"))
    )
    (net (code "105") (name "unconnected-(IC9-Pad1)") (class "Default")
      (node (ref "IC9") (pin "1") (pinfunction "1_1") (pintype "passive"))
    )
    (net (code "106") (name "unconnected-(IC9-Pad20)") (class "Default")
      (node (ref "IC9") (pin "20") (pinfunction "20_20") (pintype "passive"))
    )
  )
)
